# Esp32.net
KiCad netlist of a schematic drawn in Altium Designer
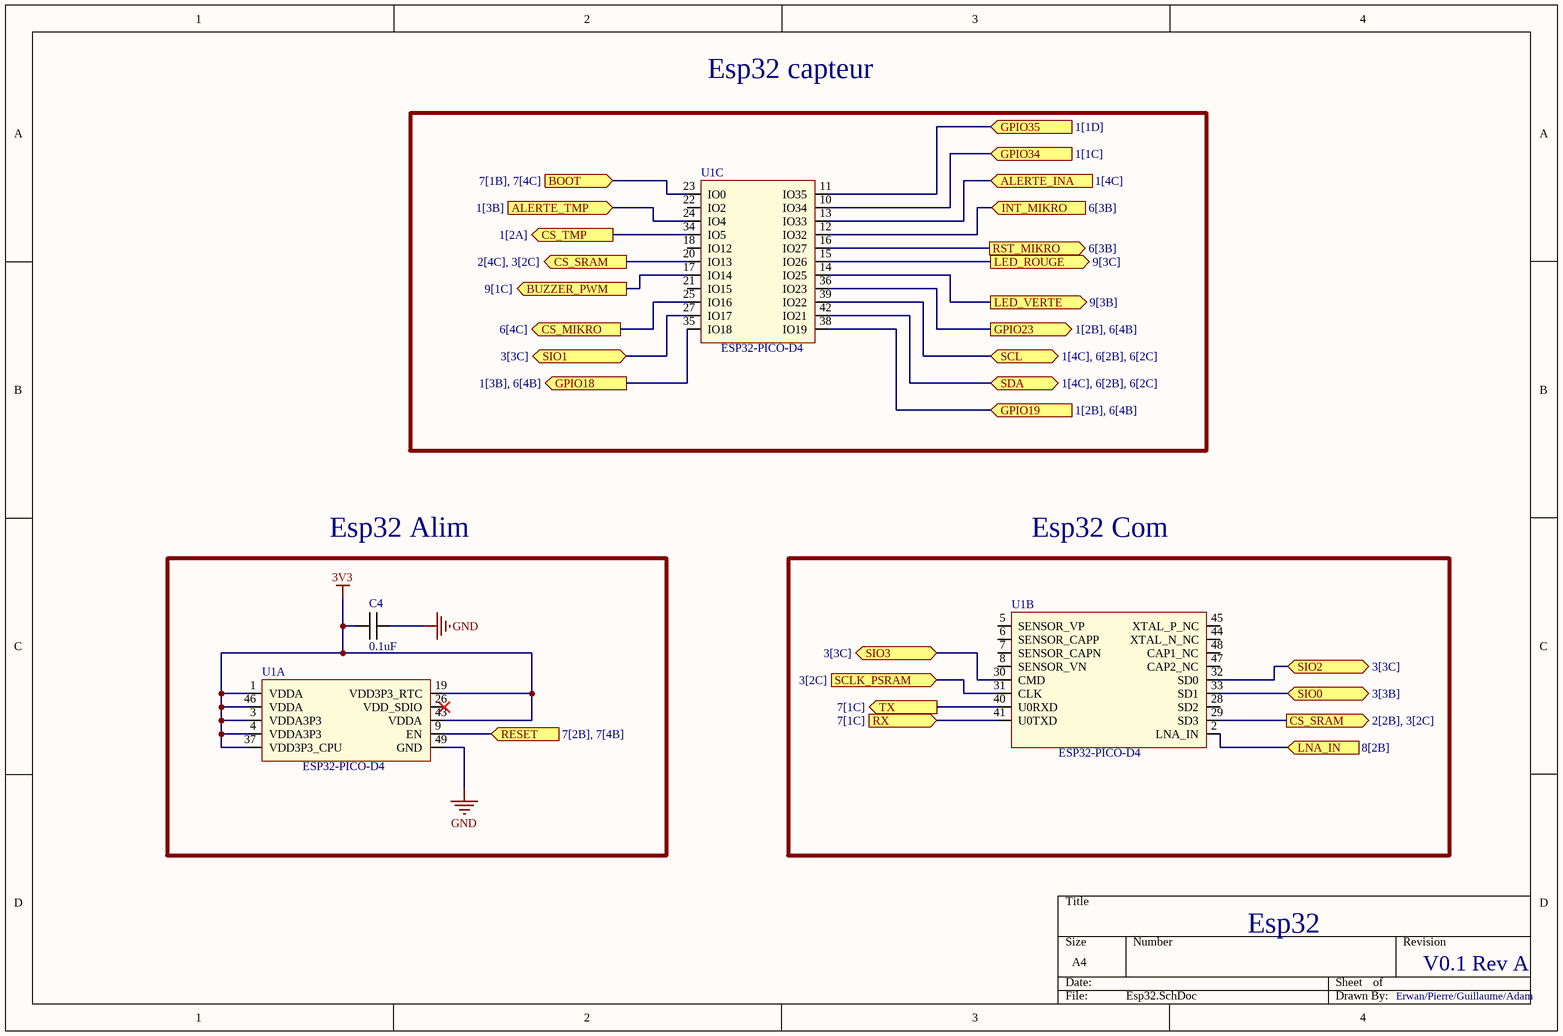
[diagram p0: Esp32.SchDoc]

(export (version "E")
  (design (tool "Eeschema 10.0.6"))
  (components
    (comp (ref "C4")
      (value "0.1uF")
      (footprint "CAPC1005X06N")
      (libsource (lib "SCHLibrary") (part "Capacitor"))
    )
    (comp (ref "U1")
      (value "ESP32-PICO-D4")
      (footprint "PQFN50P700X700X104_HS-49N")
      (libsource (lib "SCHLibrary") (part "ESP32"))
    )
  )
  (nets
    (net (code "1") (name "/ALERTE_INA") (class "Default")
      (node (ref "U1") (pin "13") (pinfunction "IO33_13") (pintype "passive"))
    )
    (net (code "2") (name "/ALERTE_TMP") (class "Default")
      (node (ref "U1") (pin "24") (pinfunction "IO4_24") (pintype "passive"))
    )
    (net (code "3") (name "/BOOT") (class "Default")
      (node (ref "U1") (pin "23") (pinfunction "IO0_23") (pintype "passive"))
    )
    (net (code "4") (name "/BUZZER_PWM") (class "Default")
      (node (ref "U1") (pin "17") (pinfunction "IO14_17") (pintype "passive"))
    )
    (net (code "5") (name "/CS_MIKRO") (class "Default")
      (node (ref "U1") (pin "25") (pinfunction "IO16_25") (pintype "passive"))
    )
    (net (code "6") (name "/CS_SRAM") (class "Default")
      (node (ref "U1") (pin "20") (pinfunction "IO13_20") (pintype "passive"))
      (node (ref "U1") (pin "29") (pinfunction "SD3_29") (pintype "passive"))
    )
    (net (code "7") (name "/CS_TMP") (class "Default")
      (node (ref "U1") (pin "34") (pinfunction "IO5_34") (pintype "passive"))
    )
    (net (code "8") (name "/GPIO18") (class "Default")
      (node (ref "U1") (pin "35") (pinfunction "IO18_35") (pintype "passive"))
    )
    (net (code "9") (name "/GPIO19") (class "Default")
      (node (ref "U1") (pin "38") (pinfunction "IO19_38") (pintype "passive"))
    )
    (net (code "10") (name "/GPIO23") (class "Default")
      (node (ref "U1") (pin "36") (pinfunction "IO23_36") (pintype "passive"))
    )
    (net (code "11") (name "/GPIO34") (class "Default")
      (node (ref "U1") (pin "10") (pinfunction "IO34_10") (pintype "passive"))
    )
    (net (code "12") (name "/GPIO35") (class "Default")
      (node (ref "U1") (pin "11") (pinfunction "IO35_11") (pintype "passive"))
    )
    (net (code "13") (name "/INT_MIKRO") (class "Default")
      (node (ref "U1") (pin "12") (pinfunction "IO32_12") (pintype "passive"))
    )
    (net (code "14") (name "/LED_ROUGE") (class "Default")
      (node (ref "U1") (pin "15") (pinfunction "IO26_15") (pintype "passive"))
    )
    (net (code "15") (name "/LED_VERTE") (class "Default")
      (node (ref "U1") (pin "14") (pinfunction "IO25_14") (pintype "passive"))
    )
    (net (code "16") (name "/LNA_IN") (class "Default")
      (node (ref "U1") (pin "2") (pinfunction "LNA_IN_2") (pintype "passive"))
    )
    (net (code "17") (name "/RESET") (class "Default")
      (node (ref "U1") (pin "9") (pinfunction "EN_9") (pintype "passive"))
    )
    (net (code "18") (name "/RST_MIKRO") (class "Default")
      (node (ref "U1") (pin "16") (pinfunction "IO27_16") (pintype "passive"))
    )
    (net (code "19") (name "/RX") (class "Default")
      (node (ref "U1") (pin "41") (pinfunction "U0TXD_41") (pintype "passive"))
    )
    (net (code "20") (name "/SCL") (class "Default")
      (node (ref "U1") (pin "39") (pinfunction "IO22_39") (pintype "passive"))
    )
    (net (code "21") (name "/SCLK_PSRAM") (class "Default")
      (node (ref "U1") (pin "31") (pinfunction "CLK_31") (pintype "passive"))
    )
    (net (code "22") (name "/SDA") (class "Default")
      (node (ref "U1") (pin "42") (pinfunction "IO21_42") (pintype "passive"))
    )
    (net (code "23") (name "/SIO0") (class "Default")
      (node (ref "U1") (pin "33") (pinfunction "SD1_33") (pintype "passive"))
    )
    (net (code "24") (name "/SIO1") (class "Default")
      (node (ref "U1") (pin "27") (pinfunction "IO17_27") (pintype "passive"))
    )
    (net (code "25") (name "/SIO2") (class "Default")
      (node (ref "U1") (pin "32") (pinfunction "SD0_32") (pintype "passive"))
    )
    (net (code "26") (name "/SIO3") (class "Default")
      (node (ref "U1") (pin "30") (pinfunction "CMD_30") (pintype "passive"))
    )
    (net (code "27") (name "/TX") (class "Default")
      (node (ref "U1") (pin "40") (pinfunction "U0RXD_40") (pintype "passive"))
    )
    (net (code "28") (name "3V3") (class "Default")
      (node (ref "C4") (pin "1") (pinfunction "1_1") (pintype "passive"))
      (node (ref "U1") (pin "1") (pinfunction "VDDA_1") (pintype "passive"))
      (node (ref "U1") (pin "19") (pinfunction "VDD3P3_RTC_19") (pintype "passive"))
      (node (ref "U1") (pin "3") (pinfunction "VDDA3P3_3") (pintype "passive"))
      (node (ref "U1") (pin "37") (pinfunction "VDD3P3_CPU_37") (pintype "passive"))
      (node (ref "U1") (pin "4") (pinfunction "VDDA3P3_4") (pintype "passive"))
      (node (ref "U1") (pin "43") (pinfunction "VDDA_43") (pintype "passive"))
      (node (ref "U1") (pin "46") (pinfunction "VDDA_46") (pintype "passive"))
    )
    (net (code "29") (name "GND") (class "Default")
      (node (ref "C4") (pin "2") (pinfunction "2_2") (pintype "passive"))
      (node (ref "U1") (pin "49") (pinfunction "GND_49") (pintype "passive"))
    )
    (net (code "30") (name "unconnected-(U1A-VDD_SDIO-Pad26)") (class "Default")
      (node (ref "U1") (pin "26") (pinfunction "VDD_SDIO_26") (pintype "passive+no_connect"))
    )
    (net (code "31") (name "unconnected-(U1B-CAP1_NC-Pad48)") (class "Default")
      (node (ref "U1") (pin "48") (pinfunction "CAP1_NC_48") (pintype "passive"))
    )
    (net (code "32") (name "unconnected-(U1B-CAP2_NC-Pad47)") (class "Default")
      (node (ref "U1") (pin "47") (pinfunction "CAP2_NC_47") (pintype "passive"))
    )
    (net (code "33") (name "unconnected-(U1B-SD2-Pad28)") (class "Default")
      (node (ref "U1") (pin "28") (pinfunction "SD2_28") (pintype "passive"))
    )
    (net (code "34") (name "unconnected-(U1B-SENSOR_CAPN-Pad7)") (class "Default")
      (node (ref "U1") (pin "7") (pinfunction "SENSOR_CAPN_7") (pintype "passive"))
    )
    (net (code "35") (name "unconnected-(U1B-SENSOR_CAPP-Pad6)") (class "Default")
      (node (ref "U1") (pin "6") (pinfunction "SENSOR_CAPP_6") (pintype "passive"))
    )
    (net (code "36") (name "unconnected-(U1B-SENSOR_VN-Pad8)") (class "Default")
      (node (ref "U1") (pin "8") (pinfunction "SENSOR_VN_8") (pintype "passive"))
    )
    (net (code "37") (name "unconnected-(U1B-SENSOR_VP-Pad5)") (class "Default")
      (node (ref "U1") (pin "5") (pinfunction "SENSOR_VP_5") (pintype "passive"))
    )
    (net (code "38") (name "unconnected-(U1B-XTAL_N_NC-Pad44)") (class "Default")
      (node (ref "U1") (pin "44") (pinfunction "XTAL_N_NC_44") (pintype "passive"))
    )
    (net (code "39") (name "unconnected-(U1B-XTAL_P_NC-Pad45)") (class "Default")
      (node (ref "U1") (pin "45") (pinfunction "XTAL_P_NC_45") (pintype "passive"))
    )
    (net (code "40") (name "unconnected-(U1C-IO2-Pad22)") (class "Default")
      (node (ref "U1") (pin "22") (pinfunction "IO2_22") (pintype "passive"))
    )
    (net (code "41") (name "unconnected-(U1C-IO12-Pad18)") (class "Default")
      (node (ref "U1") (pin "18") (pinfunction "IO12_18") (pintype "passive"))
    )
    (net (code "42") (name "unconnected-(U1C-IO15-Pad21)") (class "Default")
      (node (ref "U1") (pin "21") (pinfunction "IO15_21") (pintype "passive"))
    )
  )
)
